# sanziqi_v1_2.net
KiCad netlist of a schematic drawn in Altium Designer
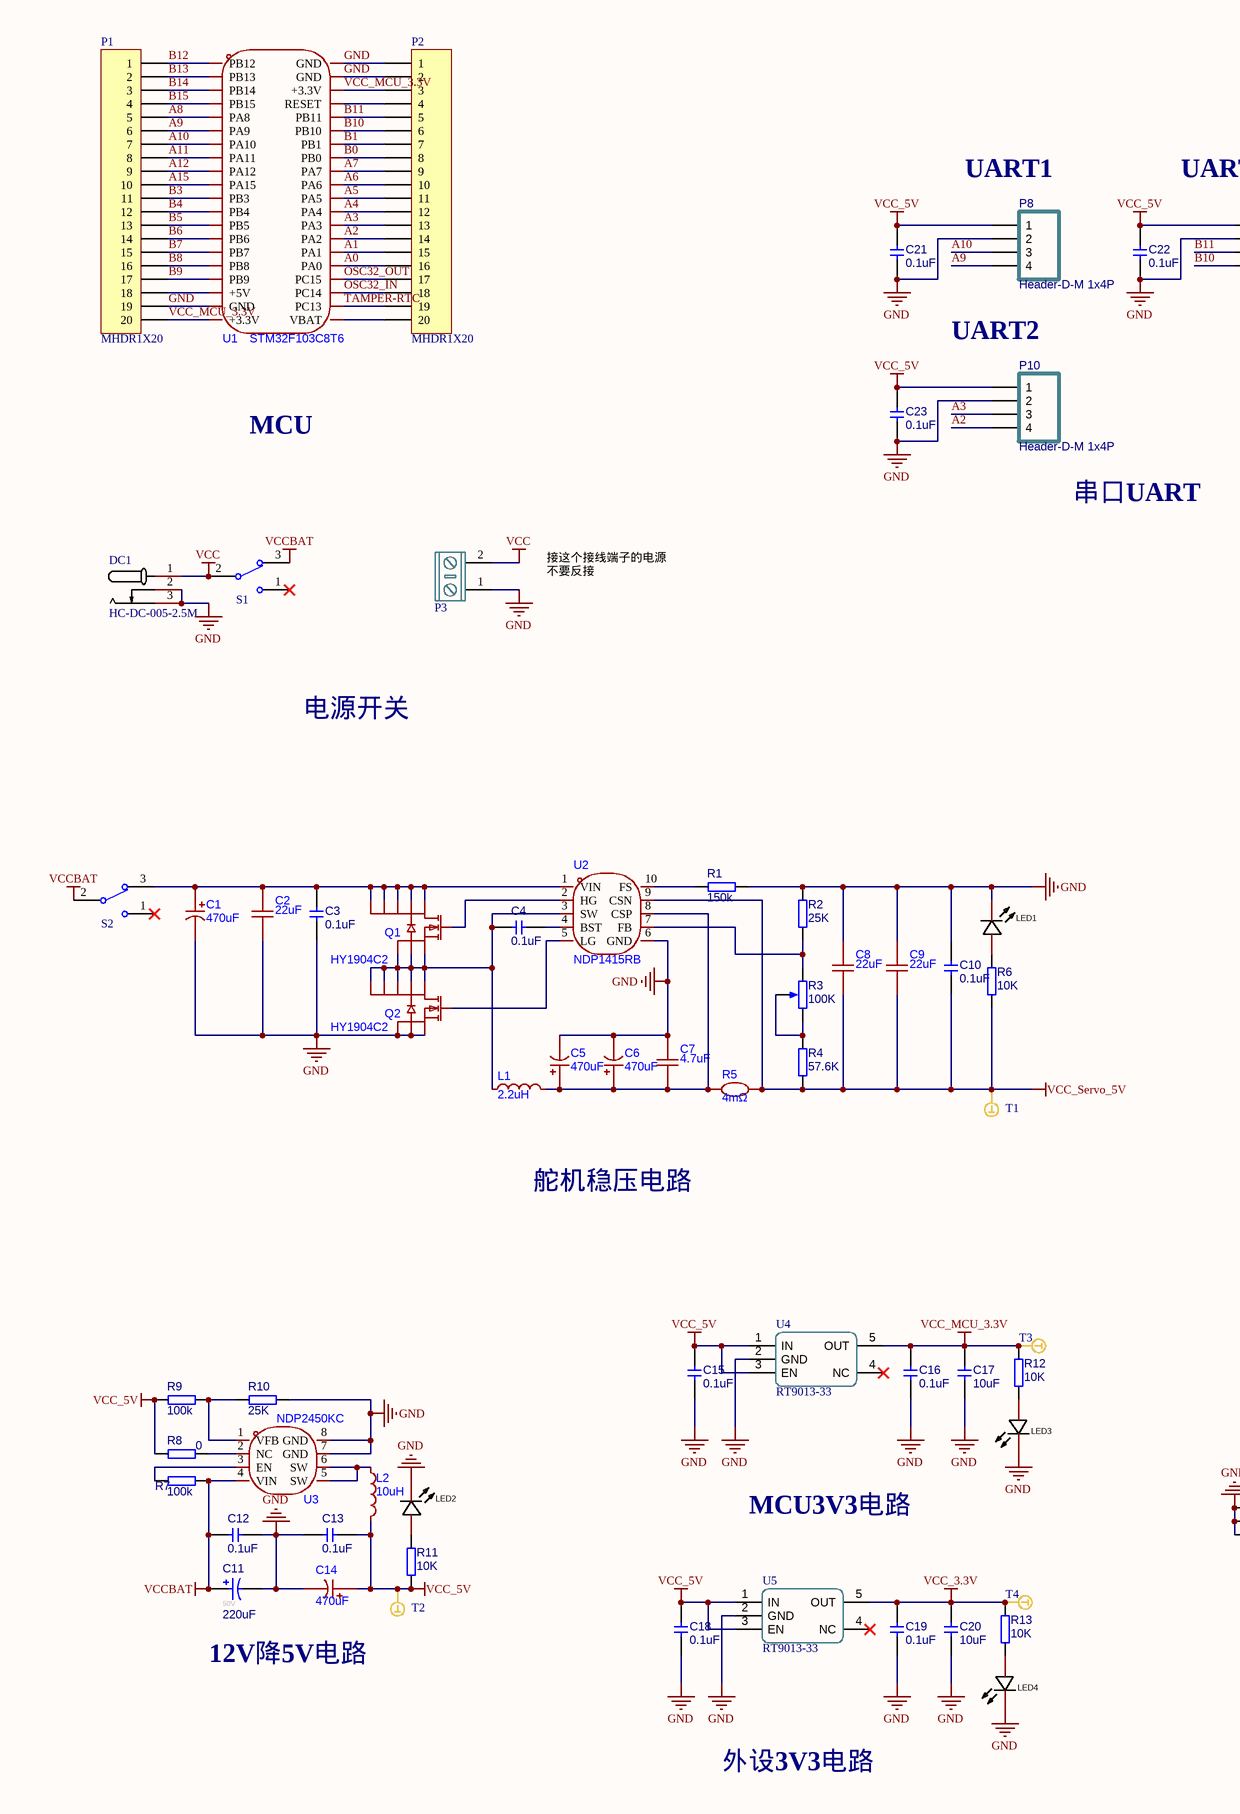
[diagram p0: sanziqi_v1.2.SchDoc, left]
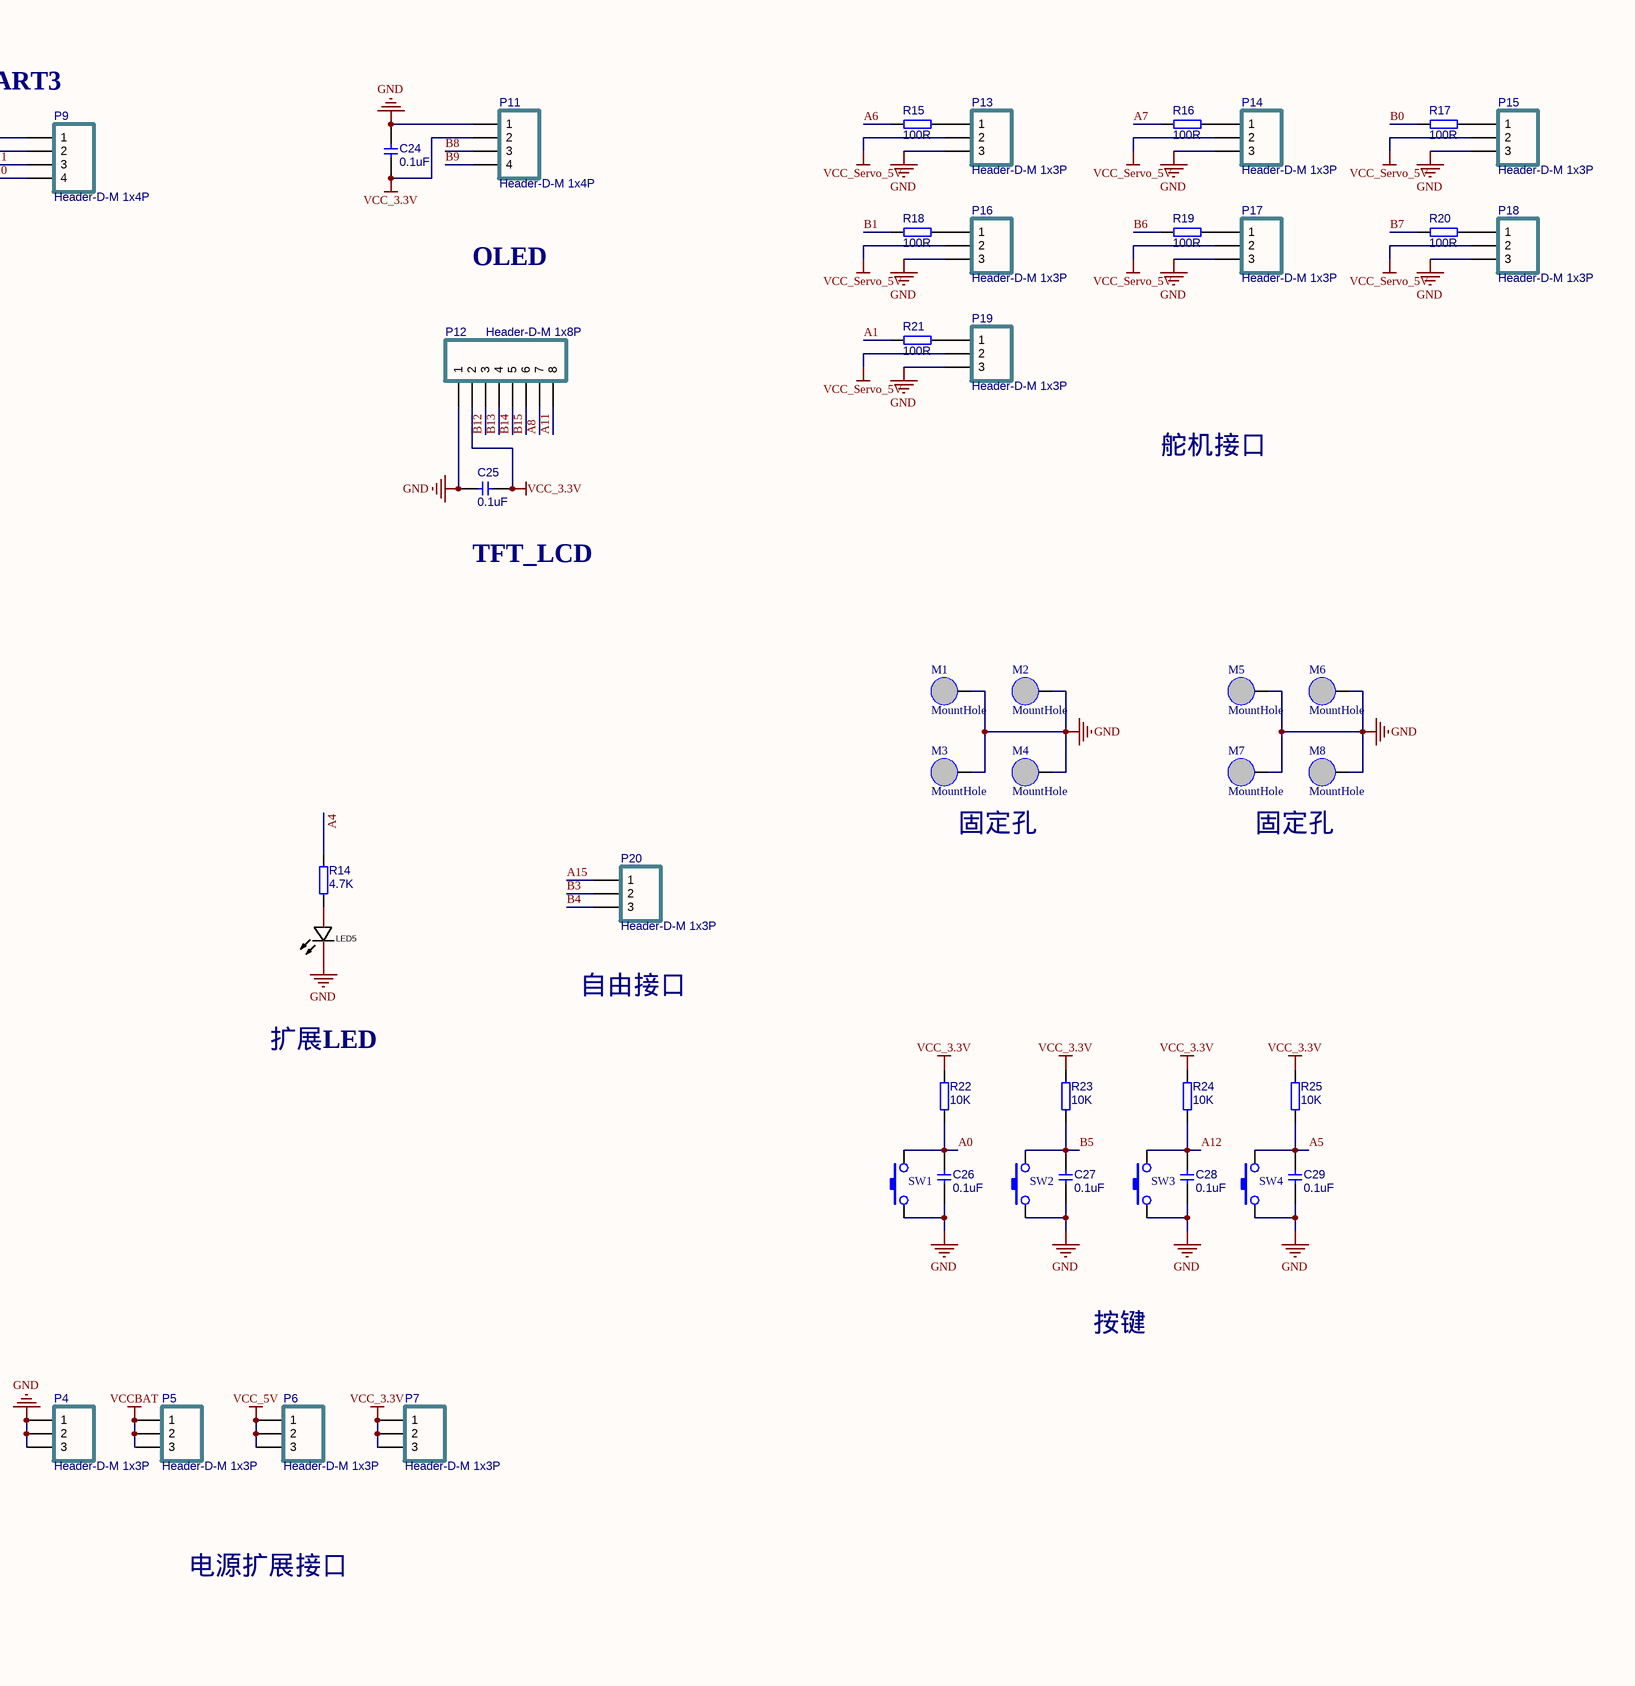
[diagram p1: sanziqi_v1.2.SchDoc, right]

(export (version "E")
  (design (tool "Eeschema 10.0.6"))
  (components
    (comp (ref "C1")
      (value "470uF")
      (footprint "CAP-TH_BD10.0-P5.00-D0.6-FD")
      (description "直插固态电容 470UF")
      (fields (field (name "MANUFACTURER") "HONOR(荣誉)") (field (name "MANUFACTURER PART") "HG1H477M1016PC"))
      (libsource (lib "sanziqi_v1.2") (part "HG1H477M1016PC"))
    )
    (comp (ref "C2")
      (value "22uF")
      (footprint "C1206")
      (fields
        (field (name "MANUFACTURER") "HRE(芯声)")
        (field (name "MANUFACTURER PART") "CGA1206X5R226M350NT")
        (field (name "TOLERANCE") "±20%")
      )
      (libsource (lib "sanziqi_v1.2") (part "Cap 22uF 1206"))
    )
    (comp (ref "C3")
      (value "0.1uF")
      (footprint "C0805")
      (description "贴片电容0805")
      (fields (field (name "Comment") "0.1uF  "))
      (libsource (lib "sanziqi_v1.2") (part "Cap 0.1uF 0805"))
    )
    (comp (ref "C4")
      (value "0.1uF")
      (footprint "C0805")
      (description "贴片电容0805")
      (fields (field (name "Comment") "0.1uF  "))
      (libsource (lib "sanziqi_v1.2") (part "Cap 0.1uF 0805"))
    )
    (comp (ref "C5")
      (value "470uF")
      (footprint "CAP-TH_BD10.0-P5.00-D0.6-FD")
      (description "直插固态电容 470UF")
      (fields (field (name "MANUFACTURER") "HONOR(荣誉)") (field (name "MANUFACTURER PART") "HG1H477M1016PC"))
      (libsource (lib "sanziqi_v1.2") (part "HG1H477M1016PC"))
    )
    (comp (ref "C6")
      (value "470uF")
      (footprint "CAP-TH_BD10.0-P5.00-D0.6-FD")
      (description "直插固态电容 470UF")
      (fields (field (name "MANUFACTURER") "HONOR(荣誉)") (field (name "MANUFACTURER PART") "HG1H477M1016PC"))
      (libsource (lib "sanziqi_v1.2") (part "HG1H477M1016PC"))
    )
    (comp (ref "C7")
      (value "4.7uF")
      (footprint "C1206")
      (fields
        (field (name "MANUFACTURER") "HRE(芯声)")
        (field (name "MANUFACTURER PART") "CGA1206X5R226M350NT")
        (field (name "TOLERANCE") "±20%")
      )
      (libsource (lib "sanziqi_v1.2") (part "Cap 22uF 1206"))
    )
    (comp (ref "C8")
      (value "22uF")
      (footprint "C1206")
      (fields
        (field (name "MANUFACTURER") "HRE(芯声)")
        (field (name "MANUFACTURER PART") "CGA1206X5R226M350NT")
        (field (name "TOLERANCE") "±20%")
      )
      (libsource (lib "sanziqi_v1.2") (part "Cap 22uF 1206"))
    )
    (comp (ref "C9")
      (value "22uF")
      (footprint "C1206")
      (fields
        (field (name "MANUFACTURER") "HRE(芯声)")
        (field (name "MANUFACTURER PART") "CGA1206X5R226M350NT")
        (field (name "TOLERANCE") "±20%")
      )
      (libsource (lib "sanziqi_v1.2") (part "Cap 22uF 1206"))
    )
    (comp (ref "C10")
      (value "0.1uF")
      (footprint "C0805")
      (description "贴片电容0805")
      (fields (field (name "Comment") "0.1uF  "))
      (libsource (lib "sanziqi_v1.2") (part "Cap 0.1uF 0805"))
    )
    (comp (ref "C11")
      (value "220uF")
      (footprint "CAP-TH_BD8.0-P3.50-D0.6-FD")
      (description "直插电解电容 220uF")
      (fields (field (name "VOLTAGE") "50V") (field (name "Comment") "220uF 50V 铝电解"))
      (libsource (lib "sanziqi_v1.2") (part "220uF 50V"))
    )
    (comp (ref "C12")
      (value "0.1uF")
      (footprint "C0805")
      (description "贴片电容0805")
      (fields (field (name "Comment") "0.1uF  "))
      (libsource (lib "sanziqi_v1.2") (part "0.1uF 0805"))
    )
    (comp (ref "C13")
      (value "0.1uF")
      (footprint "C0805")
      (description "贴片电容0805")
      (fields (field (name "Comment") "0.1uF  "))
      (libsource (lib "sanziqi_v1.2") (part "0.1uF 0805"))
    )
    (comp (ref "C14")
      (value "470uF")
      (footprint "CAP-TH_BD10.0-P5.00-D0.6-FD")
      (description "直插固态电容 470UF")
      (fields (field (name "MANUFACTURER") "HONOR(荣誉)") (field (name "MANUFACTURER PART") "HG1H477M1016PC"))
      (libsource (lib "sanziqi_v1.2") (part "HG1H477M1016PC"))
    )
    (comp (ref "C15")
      (value "0.1uF")
      (footprint "C0805")
      (description "贴片电容0805")
      (fields (field (name "Comment") "0.1uF  "))
      (libsource (lib "sanziqi_v1.2") (part "Cap 0.1uF 0805"))
    )
    (comp (ref "C16")
      (value "0.1uF")
      (footprint "C0805")
      (description "贴片电容0805")
      (fields (field (name "Comment") "0.1uF  "))
      (libsource (lib "sanziqi_v1.2") (part "Cap 0.1uF 0805"))
    )
    (comp (ref "C17")
      (value "10uF")
      (footprint "C0805")
      (description "贴片电容0805")
      (fields (field (name "Comment") "10uF  "))
      (libsource (lib "sanziqi_v1.2") (part "Cap 10uF 0805"))
    )
    (comp (ref "C18")
      (value "0.1uF")
      (footprint "C0805")
      (description "贴片电容0805")
      (fields (field (name "Comment") "0.1uF  "))
      (libsource (lib "sanziqi_v1.2") (part "Cap 0.1uF 0805"))
    )
    (comp (ref "C19")
      (value "0.1uF")
      (footprint "C0805")
      (description "贴片电容0805")
      (fields (field (name "Comment") "0.1uF  "))
      (libsource (lib "sanziqi_v1.2") (part "Cap 0.1uF 0805"))
    )
    (comp (ref "C20")
      (value "10uF")
      (footprint "C0805")
      (description "贴片电容0805")
      (fields (field (name "Comment") "10uF  "))
      (libsource (lib "sanziqi_v1.2") (part "Cap 10uF 0805"))
    )
    (comp (ref "C21")
      (value "0.1uF")
      (footprint "C0805")
      (description "贴片电容0805")
      (fields (field (name "Comment") "0.1uF  "))
      (libsource (lib "sanziqi_v1.2") (part "Cap 0.1uF 0805"))
    )
    (comp (ref "C22")
      (value "0.1uF")
      (footprint "C0805")
      (description "贴片电容0805")
      (fields (field (name "Comment") "0.1uF  "))
      (libsource (lib "sanziqi_v1.2") (part "Cap 0.1uF 0805"))
    )
    (comp (ref "C23")
      (value "0.1uF")
      (footprint "C0805")
      (description "贴片电容0805")
      (fields (field (name "Comment") "0.1uF  "))
      (libsource (lib "sanziqi_v1.2") (part "Cap 0.1uF 0805"))
    )
    (comp (ref "C24")
      (value "0.1uF")
      (footprint "C0805")
      (description "贴片电容0805")
      (fields (field (name "Comment") "0.1uF  "))
      (libsource (lib "sanziqi_v1.2") (part "Cap 0.1uF 0805"))
    )
    (comp (ref "C25")
      (value "0.1uF")
      (footprint "C0805")
      (description "贴片电容0805")
      (fields (field (name "Comment") "0.1uF  "))
      (libsource (lib "sanziqi_v1.2") (part "Cap 0.1uF 0805"))
    )
    (comp (ref "C26")
      (value "0.1uF")
      (footprint "C0805")
      (description "贴片电容0805")
      (fields (field (name "Comment") "0.1uF  "))
      (libsource (lib "sanziqi_v1.2") (part "Cap 0.1uF 0805"))
    )
    (comp (ref "C27")
      (value "0.1uF")
      (footprint "C0805")
      (description "贴片电容0805")
      (fields (field (name "Comment") "0.1uF  "))
      (libsource (lib "sanziqi_v1.2") (part "Cap 0.1uF 0805"))
    )
    (comp (ref "C28")
      (value "0.1uF")
      (footprint "C0805")
      (description "贴片电容0805")
      (fields (field (name "Comment") "0.1uF  "))
      (libsource (lib "sanziqi_v1.2") (part "Cap 0.1uF 0805"))
    )
    (comp (ref "C29")
      (value "0.1uF")
      (footprint "C0805")
      (description "贴片电容0805")
      (fields (field (name "Comment") "0.1uF  "))
      (libsource (lib "sanziqi_v1.2") (part "Cap 0.1uF 0805"))
    )
    (comp (ref "DC1")
      (value "HC-DC-005-2.5M")
      (footprint "DC-005")
      (fields (field (name "MANUFACTURER") "HCTL(华灿天禄)") (field (name "NAME") "HC-DC-005-2.5M"))
      (libsource (lib "sanziqi_v1.2") (part "HC-DC-005-2.5M"))
    )
    (comp (ref "L1")
      (value "2.2uH")
      (footprint "IND-SMD_L11.5-W10.0_FXL1040")
      (fields
        (field (name "MANUFACTURER") "cjiang(长江微电)")
        (field (name "MANUFACTURER PART") "FXL1050-2R2-M")
        (field (name "TOLERANCE") "±20%")
      )
      (libsource (lib "sanziqi_v1.2") (part "FXL1050-2R2-M"))
    )
    (comp (ref "L2")
      (value "10uH")
      (footprint "IND-SMD_L11.5-W10.0_FXL1040")
      (fields
        (field (name "MANUFACTURER") "cjiang(长江微电)")
        (field (name "MANUFACTURER PART") "FXL1040-100-M")
        (field (name "TOLERANCE") "±20%")
      )
      (libsource (lib "sanziqi_v1.2") (part "FXL1040-100-M"))
    )
    (comp (ref "LED1")
      (value "NCD0805R1")
      (footprint "LED0805-R-RD")
      (fields (field (name "MANUFACTURER") "国星光电"))
      (libsource (lib "sanziqi_v1.2") (part "LED"))
    )
    (comp (ref "LED2")
      (value "NCD0805R1")
      (footprint "LED0805-R-RD")
      (fields (field (name "MANUFACTURER") "国星光电"))
      (libsource (lib "sanziqi_v1.2") (part "LED"))
    )
    (comp (ref "LED3")
      (value "NCD0805R1")
      (footprint "LED0805-R-RD")
      (fields (field (name "MANUFACTURER") "国星光电"))
      (libsource (lib "sanziqi_v1.2") (part "LED"))
    )
    (comp (ref "LED4")
      (value "NCD0805R1")
      (footprint "LED0805-R-RD")
      (fields (field (name "MANUFACTURER") "国星光电"))
      (libsource (lib "sanziqi_v1.2") (part "LED"))
    )
    (comp (ref "LED5")
      (value "NCD0805R1")
      (footprint "LED0805-R-RD")
      (fields (field (name "MANUFACTURER") "国星光电"))
      (libsource (lib "sanziqi_v1.2") (part "LED"))
    )
    (comp (ref "M1")
      (value "MountHole")
      (footprint "M3-MountHole")
      (description "固定孔")
      (libsource (lib "sanziqi_v1.2") (part "MountHole"))
    )
    (comp (ref "M2")
      (value "MountHole")
      (footprint "M3-MountHole")
      (description "固定孔")
      (libsource (lib "sanziqi_v1.2") (part "MountHole"))
    )
    (comp (ref "M3")
      (value "MountHole")
      (footprint "M3-MountHole")
      (description "固定孔")
      (libsource (lib "sanziqi_v1.2") (part "MountHole"))
    )
    (comp (ref "M4")
      (value "MountHole")
      (footprint "M3-MountHole")
      (description "固定孔")
      (libsource (lib "sanziqi_v1.2") (part "MountHole"))
    )
    (comp (ref "M5")
      (value "MountHole")
      (footprint "M3-MountHole")
      (description "固定孔")
      (libsource (lib "sanziqi_v1.2") (part "MountHole"))
    )
    (comp (ref "M6")
      (value "MountHole")
      (footprint "M3-MountHole")
      (description "固定孔")
      (libsource (lib "sanziqi_v1.2") (part "MountHole"))
    )
    (comp (ref "M7")
      (value "MountHole")
      (footprint "M3-MountHole")
      (description "固定孔")
      (libsource (lib "sanziqi_v1.2") (part "MountHole"))
    )
    (comp (ref "M8")
      (value "MountHole")
      (footprint "M3-MountHole")
      (description "固定孔")
      (libsource (lib "sanziqi_v1.2") (part "MountHole"))
    )
    (comp (ref "P1")
      (value "MHDR1X20")
      (footprint "HDR2.54-LI-20P")
      (description "Header, 20-Pin")
      (fields (field (name "PUBLISHER") "Altium Limited"))
      (libsource (lib "sanziqi_v1.2") (part "MHDR1X20"))
    )
    (comp (ref "P2")
      (value "MHDR1X20")
      (footprint "HDR2.54-LI-20P")
      (description "Header, 20-Pin")
      (fields (field (name "PUBLISHER") "Altium Limited"))
      (libsource (lib "") (part "MHDR1X20_1"))
    )
    (comp (ref "P3")
      (value "KF/WJ/DG 30x connecter")
      (footprint "KF/WJ/DG 301-2p-5.0mm")
      (description "接线端子 2Pin")
      (libsource (lib "sanziqi_v1.2") (part "KF/WJ/DG 30x"))
    )
    (comp (ref "P4")
      (value "Header-D-M 1x3P")
      (footprint "HDR1X3-M")
      (description "1x3pin, 直插, 排针")
      (libsource (lib "sanziqi_v1.2") (part "Header-D-M 1x3P"))
    )
    (comp (ref "P5")
      (value "Header-D-M 1x3P")
      (footprint "HDR1X3-M")
      (description "1x3pin, 直插, 排针")
      (libsource (lib "sanziqi_v1.2") (part "Header-D-M 1x3P"))
    )
    (comp (ref "P6")
      (value "Header-D-M 1x3P")
      (footprint "HDR1X3-M")
      (description "1x3pin, 直插, 排针")
      (libsource (lib "sanziqi_v1.2") (part "Header-D-M 1x3P"))
    )
    (comp (ref "P7")
      (value "Header-D-M 1x3P")
      (footprint "HDR1X3-M")
      (description "1x3pin, 直插, 排针")
      (libsource (lib "sanziqi_v1.2") (part "Header-D-M 1x3P"))
    )
    (comp (ref "P8")
      (value "Header-D-M 1x4P")
      (footprint "HDR1X4-M")
      (description "1x4pin, 直插, 排针")
      (libsource (lib "sanziqi_v1.2") (part "Header-D-M 1x4P"))
    )
    (comp (ref "P9")
      (value "Header-D-M 1x4P")
      (footprint "HDR1X4-M")
      (description "1x4pin, 直插, 排针")
      (libsource (lib "sanziqi_v1.2") (part "Header-D-M 1x4P"))
    )
    (comp (ref "P10")
      (value "Header-D-M 1x4P")
      (footprint "HDR1X4-M")
      (description "1x4pin, 直插, 排针")
      (libsource (lib "sanziqi_v1.2") (part "Header-D-M 1x4P"))
    )
    (comp (ref "P11")
      (value "Header-D-M 1x4P")
      (footprint "HDR1X4-M")
      (description "1x4pin, 直插, 排针")
      (libsource (lib "sanziqi_v1.2") (part "Header-D-M 1x4P"))
    )
    (comp (ref "P12")
      (value "Header-D-M 1x8P")
      (footprint "HDR1X8-M")
      (description "1x8pin, 直插, 排针")
      (libsource (lib "sanziqi_v1.2") (part "Header-D-M 1x8P"))
    )
    (comp (ref "P13")
      (value "Header-D-M 1x3P")
      (footprint "HDR1X3-M")
      (description "1x3pin, 直插, 排针")
      (libsource (lib "sanziqi_v1.2") (part "Header-D-M 1x3P"))
    )
    (comp (ref "P14")
      (value "Header-D-M 1x3P")
      (footprint "HDR1X3-M")
      (description "1x3pin, 直插, 排针")
      (libsource (lib "sanziqi_v1.2") (part "Header-D-M 1x3P"))
    )
    (comp (ref "P15")
      (value "Header-D-M 1x3P")
      (footprint "HDR1X3-M")
      (description "1x3pin, 直插, 排针")
      (libsource (lib "sanziqi_v1.2") (part "Header-D-M 1x3P"))
    )
    (comp (ref "P16")
      (value "Header-D-M 1x3P")
      (footprint "HDR1X3-M")
      (description "1x3pin, 直插, 排针")
      (libsource (lib "sanziqi_v1.2") (part "Header-D-M 1x3P"))
    )
    (comp (ref "P17")
      (value "Header-D-M 1x3P")
      (footprint "HDR1X3-M")
      (description "1x3pin, 直插, 排针")
      (libsource (lib "sanziqi_v1.2") (part "Header-D-M 1x3P"))
    )
    (comp (ref "P18")
      (value "Header-D-M 1x3P")
      (footprint "HDR1X3-M")
      (description "1x3pin, 直插, 排针")
      (libsource (lib "sanziqi_v1.2") (part "Header-D-M 1x3P"))
    )
    (comp (ref "P19")
      (value "Header-D-M 1x3P")
      (footprint "HDR1X3-M")
      (description "1x3pin, 直插, 排针")
      (libsource (lib "sanziqi_v1.2") (part "Header-D-M 1x3P"))
    )
    (comp (ref "P20")
      (value "Header-D-M 1x3P")
      (footprint "HDR1X3-M")
      (description "1x3pin, 直插, 排针")
      (libsource (lib "sanziqi_v1.2") (part "Header-D-M 1x3P"))
    )
    (comp (ref "Q1")
      (value "HY1904C2")
      (footprint "DFN-8_L5.9-W5.2-P1.27-LS6.2-BL")
      (fields (field (name "MANUFACTURER") "HUAYI(华羿微)"))
      (libsource (lib "sanziqi_v1.2") (part "HY1904C2"))
    )
    (comp (ref "Q2")
      (value "HY1904C2")
      (footprint "DFN-8_L5.9-W5.2-P1.27-LS6.2-BL")
      (fields (field (name "MANUFACTURER") "HUAYI(华羿微)"))
      (libsource (lib "sanziqi_v1.2") (part "HY1904C2"))
    )
    (comp (ref "R1")
      (value "150k")
      (footprint "R0805")
      (description "贴片电阻")
      (fields (field (name "POWER") "1/8W") (field (name "TOLERANCE") "±1%"))
      (libsource (lib "sanziqi_v1.2") (part "Res-Chip-150K"))
    )
    (comp (ref "R2")
      (value "25K")
      (footprint "R0805")
      (description "贴片电阻")
      (fields (field (name "POWER") "1/8W") (field (name "TOLERANCE") "±1%"))
      (libsource (lib "sanziqi_v1.2") (part "Res-Chip-25K"))
    )
    (comp (ref "R3")
      (value "100K")
      (footprint "RESPOT3296W")
      (description "可调电阻")
      (libsource (lib "sanziqi_v1.2") (part "Res-Adj-3p"))
    )
    (comp (ref "R4")
      (value "57.6K")
      (footprint "R0805")
      (description "贴片电阻")
      (fields (field (name "POWER") "1/8W") (field (name "TOLERANCE") "±1%"))
      (libsource (lib "sanziqi_v1.2") (part "Res-Chip-57.6K"))
    )
    (comp (ref "R5")
      (value "4mΩ")
      (footprint "RES-SMD_L6.4-W3.2-R2512")
      (fields
        (field (name "MANUFACTURER") "Milliohm(毫欧)")
        (field (name "MANUFACTURER PART") "HoJLR2512-3W-4mR-1%")
        (field (name "TOLERANCE") "±1%")
      )
      (libsource (lib "sanziqi_v1.2") (part "Res-Chip-4mR-2512-3W"))
    )
    (comp (ref "R6")
      (value "10K")
      (footprint "R0805")
      (description "贴片电阻")
      (fields (field (name "POWER") "1/8W") (field (name "TOLERANCE") "±1%"))
      (libsource (lib "sanziqi_v1.2") (part "Res-Chip-4.7K"))
    )
    (comp (ref "R7")
      (value "100k")
      (footprint "R0805")
      (description "贴片电阻")
      (fields (field (name "POWER") "1/8W") (field (name "TOLERANCE") "±1%"))
      (libsource (lib "sanziqi_v1.2") (part "Res-Chip-100K"))
    )
    (comp (ref "R8")
      (value "0")
      (footprint "R0805")
      (description "贴片电阻")
      (fields (field (name "POWER") "1/8W") (field (name "TOLERANCE") "±1%"))
      (libsource (lib "sanziqi_v1.2") (part "Res-Chip-0"))
    )
    (comp (ref "R9")
      (value "100k")
      (footprint "R0805")
      (description "贴片电阻")
      (fields (field (name "POWER") "1/8W") (field (name "TOLERANCE") "±1%"))
      (libsource (lib "sanziqi_v1.2") (part "Res-Chip-100K"))
    )
    (comp (ref "R10")
      (value "25K")
      (footprint "R0805")
      (description "贴片电阻")
      (fields (field (name "POWER") "1/8W") (field (name "TOLERANCE") "±1%"))
      (libsource (lib "sanziqi_v1.2") (part "Res-Chip-25K"))
    )
    (comp (ref "R11")
      (value "10K")
      (footprint "R0805")
      (description "贴片电阻")
      (fields (field (name "POWER") "1/8W") (field (name "TOLERANCE") "±1%"))
      (libsource (lib "sanziqi_v1.2") (part "Res-Chip-4.7K"))
    )
    (comp (ref "R12")
      (value "10K")
      (footprint "R0805")
      (description "贴片电阻")
      (fields (field (name "POWER") "1/8W") (field (name "TOLERANCE") "±1%"))
      (libsource (lib "sanziqi_v1.2") (part "Res-Chip-4.7K"))
    )
    (comp (ref "R13")
      (value "10K")
      (footprint "R0805")
      (description "贴片电阻")
      (fields (field (name "POWER") "1/8W") (field (name "TOLERANCE") "±1%"))
      (libsource (lib "sanziqi_v1.2") (part "Res-Chip-4.7K"))
    )
    (comp (ref "R14")
      (value "4.7K")
      (footprint "R0805")
      (description "贴片电阻")
      (fields (field (name "POWER") "1/8W") (field (name "TOLERANCE") "±1%"))
      (libsource (lib "sanziqi_v1.2") (part "Res-Chip-4.7K"))
    )
    (comp (ref "R15")
      (value "100R")
      (footprint "R0805")
      (description "贴片电阻")
      (fields (field (name "POWER") "1/8W") (field (name "TOLERANCE") "±1%"))
      (libsource (lib "sanziqi_v1.2") (part "Res-Chip-100R"))
    )
    (comp (ref "R16")
      (value "100R")
      (footprint "R0805")
      (description "贴片电阻")
      (fields (field (name "POWER") "1/8W") (field (name "TOLERANCE") "±1%"))
      (libsource (lib "sanziqi_v1.2") (part "Res-Chip-100R"))
    )
    (comp (ref "R17")
      (value "100R")
      (footprint "R0805")
      (description "贴片电阻")
      (fields (field (name "POWER") "1/8W") (field (name "TOLERANCE") "±1%"))
      (libsource (lib "sanziqi_v1.2") (part "Res-Chip-100R"))
    )
    (comp (ref "R18")
      (value "100R")
      (footprint "R0805")
      (description "贴片电阻")
      (fields (field (name "POWER") "1/8W") (field (name "TOLERANCE") "±1%"))
      (libsource (lib "sanziqi_v1.2") (part "Res-Chip-100R"))
    )
    (comp (ref "R19")
      (value "100R")
      (footprint "R0805")
      (description "贴片电阻")
      (fields (field (name "POWER") "1/8W") (field (name "TOLERANCE") "±1%"))
      (libsource (lib "sanziqi_v1.2") (part "Res-Chip-100R"))
    )
    (comp (ref "R20")
      (value "100R")
      (footprint "R0805")
      (description "贴片电阻")
      (fields (field (name "POWER") "1/8W") (field (name "TOLERANCE") "±1%"))
      (libsource (lib "sanziqi_v1.2") (part "Res-Chip-100R"))
    )
    (comp (ref "R21")
      (value "100R")
      (footprint "R0805")
      (description "贴片电阻")
      (fields (field (name "POWER") "1/8W") (field (name "TOLERANCE") "±1%"))
      (libsource (lib "sanziqi_v1.2") (part "Res-Chip-100R"))
    )
    (comp (ref "R22")
      (value "10K")
      (footprint "R0805")
      (description "贴片电阻")
      (fields (field (name "POWER") "1/8W") (field (name "TOLERANCE") "±1%"))
      (libsource (lib "sanziqi_v1.2") (part "Res-Chip-10K"))
    )
    (comp (ref "R23")
      (value "10K")
      (footprint "R0805")
      (description "贴片电阻")
      (fields (field (name "POWER") "1/8W") (field (name "TOLERANCE") "±1%"))
      (libsource (lib "sanziqi_v1.2") (part "Res-Chip-10K"))
    )
    (comp (ref "R24")
      (value "10K")
      (footprint "R0805")
      (description "贴片电阻")
      (fields (field (name "POWER") "1/8W") (field (name "TOLERANCE") "±1%"))
      (libsource (lib "sanziqi_v1.2") (part "Res-Chip-10K"))
    )
    (comp (ref "R25")
      (value "10K")
      (footprint "R0805")
      (description "贴片电阻")
      (fields (field (name "POWER") "1/8W") (field (name "TOLERANCE") "±1%"))
      (libsource (lib "sanziqi_v1.2") (part "Res-Chip-10K"))
    )
    (comp (ref "S1")
      (value "SW-SPDT")
      (footprint "SS12D10")
      (description "单刀双掷开关 3脚船型、钮子、拨动开关 SPDT Subminiature Toggle Switch")
      (fields (field (name "PUBLISHER") "Altium Limited"))
      (libsource (lib "sanziqi_v1.2") (part "SW-SPDT"))
    )
    (comp (ref "S2")
      (value "SW-SPDT")
      (footprint "SS12D10")
      (description "单刀双掷开关 3脚船型、钮子、拨动开关 SPDT Subminiature Toggle Switch")
      (fields (field (name "PUBLISHER") "Altium Limited"))
      (libsource (lib "sanziqi_v1.2") (part "SW-SPDT"))
    )
    (comp (ref "SW1")
      (value "SW-PB_V")
      (footprint "TSW SMD-3*6*2.5")
      (description "SWITCH")
      (libsource (lib "sanziqi_v1.2") (part "SW-PB_V"))
    )
    (comp (ref "SW2")
      (value "SW-PB_V")
      (footprint "TSW SMD-3*6*2.5")
      (description "SWITCH")
      (libsource (lib "sanziqi_v1.2") (part "SW-PB_V"))
    )
    (comp (ref "SW3")
      (value "SW-PB_V")
      (footprint "TSW SMD-3*6*2.5")
      (description "SWITCH")
      (libsource (lib "sanziqi_v1.2") (part "SW-PB_V"))
    )
    (comp (ref "SW4")
      (value "SW-PB_V")
      (footprint "TSW SMD-3*6*2.5")
      (description "SWITCH")
      (libsource (lib "sanziqi_v1.2") (part "SW-PB_V"))
    )
    (comp (ref "T1")
      (value "Testpoint-Pad")
      (footprint "testpoint-pad-1mm")
      (description "测试点，就是个焊盘")
      (libsource (lib "sanziqi_v1.2") (part "Testpoint-Pad-S"))
    )
    (comp (ref "T2")
      (value "Testpoint-Pad")
      (footprint "testpoint-pad-1mm")
      (description "测试点，就是个焊盘")
      (libsource (lib "sanziqi_v1.2") (part "Testpoint-Pad-S"))
    )
    (comp (ref "T3")
      (value "Testpoint-Pad")
      (footprint "testpoint-pad-1mm")
      (description "测试点，就是个焊盘")
      (libsource (lib "sanziqi_v1.2") (part "Testpoint-Pad-S"))
    )
    (comp (ref "T4")
      (value "Testpoint-Pad")
      (footprint "testpoint-pad-1mm")
      (description "测试点，就是个焊盘")
      (libsource (lib "sanziqi_v1.2") (part "Testpoint-Pad-S"))
    )
    (comp (ref "U1")
      (value "STM32F103C8T6")
      (footprint "CONN-TH_L53.3-W22.9_STM32F103C8T6-CARD")
      (fields
        (field (name "MANUFACTURER") "立创开发板")
        (field (name "MANUFACTURER PART") "LCKFB-DKX-STM32F103C8T6")
      )
      (libsource (lib "sanziqi_v1.2") (part "STM32F103C8T6"))
    )
    (comp (ref "U2")
      (value "NDP1415RB")
      (footprint "SSOP-10_L4.9-W3.9-P1.00-LS6.0-BL-1")
      (fields (field (name "MANUFACTURER") "NDP(芯潭微)"))
      (libsource (lib "sanziqi_v1.2") (part "NDP1415RB"))
    )
    (comp (ref "U3")
      (value "NDP2450KC")
      (footprint "SOP-8_L4.9-W3.9-P1.27-LS6.0-BL")
      (fields (field (name "MANUFACTURER") "NDP(芯潭微)"))
      (libsource (lib "sanziqi_v1.2") (part "NDP2450KC"))
    )
    (comp (ref "U4")
      (value "RT9013-33")
      (footprint "SOT-23-5")
      (description "3.3V 500mA SOT-23-5 LDO")
      (libsource (lib "sanziqi_v1.2") (part "RT9013-33"))
    )
    (comp (ref "U5")
      (value "RT9013-33")
      (footprint "SOT-23-5")
      (description "3.3V 500mA SOT-23-5 LDO")
      (libsource (lib "sanziqi_v1.2") (part "RT9013-33"))
    )
  )
  (nets
    (net (code "1") (name "/A0") (class "Default")
      (node (ref "C26") (pin "2") (pinfunction "2_2") (pintype "passive"))
      (node (ref "P2") (pin "16") (pinfunction "16_16") (pintype "passive"))
      (node (ref "R22") (pin "1") (pinfunction "1_1") (pintype "passive"))
      (node (ref "SW1") (pin "2") (pinfunction "2_2") (pintype "passive"))
      (node (ref "U1") (pin "25") (pinfunction "PA0_25") (pintype "passive"))
    )
    (net (code "2") (name "/A1") (class "Default")
      (node (ref "P2") (pin "15") (pinfunction "15_15") (pintype "passive"))
      (node (ref "R21") (pin "1") (pinfunction "1_1") (pintype "passive"))
      (node (ref "U1") (pin "26") (pinfunction "PA1_26") (pintype "passive"))
    )
    (net (code "3") (name "/A2") (class "Default")
      (node (ref "P10") (pin "4") (pinfunction "4_4") (pintype "passive"))
      (node (ref "P2") (pin "14") (pinfunction "14_14") (pintype "passive"))
      (node (ref "U1") (pin "27") (pinfunction "PA2_27") (pintype "passive"))
    )
    (net (code "4") (name "/A3") (class "Default")
      (node (ref "P10") (pin "3") (pinfunction "3_3") (pintype "passive"))
      (node (ref "P2") (pin "13") (pinfunction "13_13") (pintype "passive"))
      (node (ref "U1") (pin "28") (pinfunction "PA3_28") (pintype "passive"))
    )
    (net (code "5") (name "/A4") (class "Default")
      (node (ref "P2") (pin "12") (pinfunction "12_12") (pintype "passive"))
      (node (ref "R14") (pin "2") (pinfunction "2_2") (pintype "passive"))
      (node (ref "U1") (pin "29") (pinfunction "PA4_29") (pintype "passive"))
    )
    (net (code "6") (name "/A5") (class "Default")
      (node (ref "C29") (pin "2") (pinfunction "2_2") (pintype "passive"))
      (node (ref "P2") (pin "11") (pinfunction "11_11") (pintype "passive"))
      (node (ref "R25") (pin "1") (pinfunction "1_1") (pintype "passive"))
      (node (ref "SW4") (pin "2") (pinfunction "2_2") (pintype "passive"))
      (node (ref "U1") (pin "30") (pinfunction "PA5_30") (pintype "passive"))
    )
    (net (code "7") (name "/A6") (class "Default")
      (node (ref "P2") (pin "10") (pinfunction "10_10") (pintype "passive"))
      (node (ref "R15") (pin "1") (pinfunction "1_1") (pintype "passive"))
      (node (ref "U1") (pin "31") (pinfunction "PA6_31") (pintype "passive"))
    )
    (net (code "8") (name "/A7") (class "Default")
      (node (ref "P2") (pin "9") (pinfunction "9_9") (pintype "passive"))
      (node (ref "R16") (pin "1") (pinfunction "1_1") (pintype "passive"))
      (node (ref "U1") (pin "32") (pinfunction "PA7_32") (pintype "passive"))
    )
    (net (code "9") (name "/A8") (class "Default")
      (node (ref "P1") (pin "5") (pinfunction "5_5") (pintype "passive"))
      (node (ref "P12") (pin "7") (pinfunction "7_7") (pintype "passive"))
      (node (ref "U1") (pin "5") (pinfunction "PA8_5") (pintype "passive"))
    )
    (net (code "10") (name "/A9") (class "Default")
      (node (ref "P1") (pin "6") (pinfunction "6_6") (pintype "passive"))
      (node (ref "P8") (pin "4") (pinfunction "4_4") (pintype "passive"))
      (node (ref "U1") (pin "6") (pinfunction "PA9_6") (pintype "passive"))
    )
    (net (code "11") (name "/A10") (class "Default")
      (node (ref "P1") (pin "7") (pinfunction "7_7") (pintype "passive"))
      (node (ref "P8") (pin "3") (pinfunction "3_3") (pintype "passive"))
      (node (ref "U1") (pin "7") (pinfunction "PA10_7") (pintype "passive"))
    )
    (net (code "12") (name "/A11") (class "Default")
      (node (ref "P1") (pin "8") (pinfunction "8_8") (pintype "passive"))
      (node (ref "P12") (pin "8") (pinfunction "8_8") (pintype "passive"))
      (node (ref "U1") (pin "8") (pinfunction "PA11_8") (pintype "passive"))
    )
    (net (code "13") (name "/A12") (class "Default")
      (node (ref "C28") (pin "2") (pinfunction "2_2") (pintype "passive"))
      (node (ref "P1") (pin "9") (pinfunction "9_9") (pintype "passive"))
      (node (ref "R24") (pin "1") (pinfunction "1_1") (pintype "passive"))
      (node (ref "SW3") (pin "2") (pinfunction "2_2") (pintype "passive"))
      (node (ref "U1") (pin "9") (pinfunction "PA12_9") (pintype "passive"))
    )
    (net (code "14") (name "/A15") (class "Default")
      (node (ref "P1") (pin "10") (pinfunction "10_10") (pintype "passive"))
      (node (ref "P20") (pin "1") (pinfunction "1_1") (pintype "passive"))
      (node (ref "U1") (pin "10") (pinfunction "PA15_10") (pintype "passive"))
    )
    (net (code "15") (name "/B0") (class "Default")
      (node (ref "P2") (pin "8") (pinfunction "8_8") (pintype "passive"))
      (node (ref "R17") (pin "1") (pinfunction "1_1") (pintype "passive"))
      (node (ref "U1") (pin "33") (pinfunction "PB0_33") (pintype "passive"))
    )
    (net (code "16") (name "/B1") (class "Default")
      (node (ref "P2") (pin "7") (pinfunction "7_7") (pintype "passive"))
      (node (ref "R18") (pin "1") (pinfunction "1_1") (pintype "passive"))
      (node (ref "U1") (pin "34") (pinfunction "PB1_34") (pintype "passive"))
    )
    (net (code "17") (name "/B3") (class "Default")
      (node (ref "P1") (pin "11") (pinfunction "11_11") (pintype "passive"))
      (node (ref "P20") (pin "2") (pinfunction "2_2") (pintype "passive"))
      (node (ref "U1") (pin "11") (pinfunction "PB3_11") (pintype "passive"))
    )
    (net (code "18") (name "/B4") (class "Default")
      (node (ref "P1") (pin "12") (pinfunction "12_12") (pintype "passive"))
      (node (ref "P20") (pin "3") (pinfunction "3_3") (pintype "passive"))
      (node (ref "U1") (pin "12") (pinfunction "PB4_12") (pintype "passive"))
    )
    (net (code "19") (name "/B5") (class "Default")
      (node (ref "C27") (pin "2") (pinfunction "2_2") (pintype "passive"))
      (node (ref "P1") (pin "13") (pinfunction "13_13") (pintype "passive"))
      (node (ref "R23") (pin "1") (pinfunction "1_1") (pintype "passive"))
      (node (ref "SW2") (pin "2") (pinfunction "2_2") (pintype "passive"))
      (node (ref "U1") (pin "13") (pinfunction "PB5_13") (pintype "passive"))
    )
    (net (code "20") (name "/B6") (class "Default")
      (node (ref "P1") (pin "14") (pinfunction "14_14") (pintype "passive"))
      (node (ref "R19") (pin "1") (pinfunction "1_1") (pintype "passive"))
      (node (ref "U1") (pin "14") (pinfunction "PB6_14") (pintype "passive"))
    )
    (net (code "21") (name "/B7") (class "Default")
      (node (ref "P1") (pin "15") (pinfunction "15_15") (pintype "passive"))
      (node (ref "R20") (pin "1") (pinfunction "1_1") (pintype "passive"))
      (node (ref "U1") (pin "15") (pinfunction "PB7_15") (pintype "passive"))
    )
    (net (code "22") (name "/B8") (class "Default")
      (node (ref "P1") (pin "16") (pinfunction "16_16") (pintype "passive"))
      (node (ref "P11") (pin "3") (pinfunction "3_3") (pintype "passive"))
      (node (ref "U1") (pin "16") (pinfunction "PB8_16") (pintype "passive"))
    )
    (net (code "23") (name "/B9") (class "Default")
      (node (ref "P1") (pin "17") (pinfunction "17_17") (pintype "passive"))
      (node (ref "P11") (pin "4") (pinfunction "4_4") (pintype "passive"))
      (node (ref "U1") (pin "17") (pinfunction "PB9_17") (pintype "passive"))
    )
    (net (code "24") (name "/B10") (class "Default")
      (node (ref "P2") (pin "6") (pinfunction "6_6") (pintype "passive"))
      (node (ref "P9") (pin "4") (pinfunction "4_4") (pintype "passive"))
      (node (ref "U1") (pin "35") (pinfunction "PB10_35") (pintype "passive"))
    )
    (net (code "25") (name "/B11") (class "Default")
      (node (ref "P2") (pin "5") (pinfunction "5_5") (pintype "passive"))
      (node (ref "P9") (pin "3") (pinfunction "3_3") (pintype "passive"))
      (node (ref "U1") (pin "36") (pinfunction "PB11_36") (pintype "passive"))
    )
    (net (code "26") (name "/B12") (class "Default")
      (node (ref "P1") (pin "1") (pinfunction "1_1") (pintype "passive"))
      (node (ref "P12") (pin "3") (pinfunction "3_3") (pintype "passive"))
      (node (ref "U1") (pin "1") (pinfunction "PB12_1") (pintype "passive"))
    )
    (net (code "27") (name "/B13") (class "Default")
      (node (ref "P1") (pin "2") (pinfunction "2_2") (pintype "passive"))
      (node (ref "P12") (pin "4") (pinfunction "4_4") (pintype "passive"))
      (node (ref "U1") (pin "2") (pinfunction "PB13_2") (pintype "passive"))
    )
    (net (code "28") (name "/B14") (class "Default")
      (node (ref "P1") (pin "3") (pinfunction "3_3") (pintype "passive"))
      (node (ref "P12") (pin "5") (pinfunction "5_5") (pintype "passive"))
      (node (ref "U1") (pin "3") (pinfunction "PB14_3") (pintype "passive"))
    )
    (net (code "29") (name "/B15") (class "Default")
      (node (ref "P1") (pin "4") (pinfunction "4_4") (pintype "passive"))
      (node (ref "P12") (pin "6") (pinfunction "6_6") (pintype "passive"))
      (node (ref "U1") (pin "4") (pinfunction "PB15_4") (pintype "passive"))
    )
    (net (code "30") (name "/OSC32_IN") (class "Default")
      (node (ref "P2") (pin "18") (pinfunction "18_18") (pintype "passive"))
      (node (ref "U1") (pin "23") (pinfunction "PC14_23") (pintype "passive"))
    )
    (net (code "31") (name "/OSC32_OUT") (class "Default")
      (node (ref "P2") (pin "17") (pinfunction "17_17") (pintype "passive"))
      (node (ref "U1") (pin "24") (pinfunction "PC15_24") (pintype "passive"))
    )
    (net (code "32") (name "/TAMPER-RTC") (class "Default")
      (node (ref "P2") (pin "19") (pinfunction "19_19") (pintype "passive"))
      (node (ref "U1") (pin "22") (pinfunction "PC13_22") (pintype "passive"))
    )
    (net (code "33") (name "GND") (class "Default")
      (node (ref "C1") (pin "2") (pinfunction "2_2") (pintype "passive"))
      (node (ref "C10") (pin "2") (pinfunction "2_2") (pintype "passive"))
      (node (ref "C11") (pin "2") (pinfunction "2_2") (pintype "passive"))
      (node (ref "C12") (pin "2") (pinfunction "2_2") (pintype "passive"))
      (node (ref "C13") (pin "1") (pinfunction "1_1") (pintype "passive"))
      (node (ref "C14") (pin "2") (pinfunction "2_2") (pintype "passive"))
      (node (ref "C15") (pin "1") (pinfunction "1_1") (pintype "passive"))
      (node (ref "C16") (pin "1") (pinfunction "1_1") (pintype "passive"))
      (node (ref "C17") (pin "1") (pinfunction "1_1") (pintype "passive"))
      (node (ref "C18") (pin "1") (pinfunction "1_1") (pintype "passive"))
      (node (ref "C19") (pin "1") (pinfunction "1_1") (pintype "passive"))
      (node (ref "C2") (pin "1") (pinfunction "1_1") (pintype "passive"))
      (node (ref "C20") (pin "1") (pinfunction "1_1") (pintype "passive"))
      (node (ref "C21") (pin "1") (pinfunction "1_1") (pintype "passive"))
      (node (ref "C22") (pin "1") (pinfunction "1_1") (pintype "passive"))
      (node (ref "C23") (pin "1") (pinfunction "1_1") (pintype "passive"))
      (node (ref "C24") (pin "2") (pinfunction "2_2") (pintype "passive"))
      (node (ref "C25") (pin "2") (pinfunction "2_2") (pintype "passive"))
      (node (ref "C26") (pin "1") (pinfunction "1_1") (pintype "passive"))
      (node (ref "C27") (pin "1") (pinfunction "1_1") (pintype "passive"))
      (node (ref "C28") (pin "1") (pinfunction "1_1") (pintype "passive"))
      (node (ref "C29") (pin "1") (pinfunction "1_1") (pintype "passive"))
      (node (ref "C3") (pin "1") (pinfunction "1_1") (pintype "passive"))
      (node (ref "C5") (pin "2") (pinfunction "2_2") (pintype "passive"))
      (node (ref "C6") (pin "2") (pinfunction "2_2") (pintype "passive"))
      (node (ref "C7") (pin "2") (pinfunction "2_2") (pintype "passive"))
      (node (ref "C8") (pin "2") (pinfunction "2_2") (pintype "passive"))
      (node (ref "C9") (pin "2") (pinfunction "2_2") (pintype "passive"))
      (node (ref "DC1") (pin "2") (pinfunction "2_2") (pintype "passive"))
      (node (ref "DC1") (pin "3") (pinfunction "3_3") (pintype "passive"))
      (node (ref "LED1") (pin "2") (pinfunction "-_2") (pintype "passive"))
      (node (ref "LED2") (pin "2") (pinfunction "-_2") (pintype "passive"))
      (node (ref "LED3") (pin "2") (pinfunction "-_2") (pintype "passive"))
      (node (ref "LED4") (pin "2") (pinfunction "-_2") (pintype "passive"))
      (node (ref "LED5") (pin "2") (pinfunction "-_2") (pintype "passive"))
      (node (ref "M1") (pin "1") (pinfunction "1_1") (pintype "passive"))
      (node (ref "M2") (pin "1") (pinfunction "1_1") (pintype "passive"))
      (node (ref "M3") (pin "1") (pinfunction "1_1") (pintype "passive"))
      (node (ref "M4") (pin "1") (pinfunction "1_1") (pintype "passive"))
      (node (ref "M5") (pin "1") (pinfunction "1_1") (pintype "passive"))
      (node (ref "M6") (pin "1") (pinfunction "1_1") (pintype "passive"))
      (node (ref "M7") (pin "1") (pinfunction "1_1") (pintype "passive"))
      (node (ref "M8") (pin "1") (pinfunction "1_1") (pintype "passive"))
      (node (ref "P1") (pin "19") (pinfunction "19_19") (pintype "passive"))
      (node (ref "P10") (pin "2") (pinfunction "2_2") (pintype "passive"))
      (node (ref "P11") (pin "1") (pinfunction "1_1") (pintype "passive"))
      (node (ref "P12") (pin "1") (pinfunction "1_1") (pintype "passive"))
      (node (ref "P13") (pin "3") (pinfunction "3_3") (pintype "passive"))
      (node (ref "P14") (pin "3") (pinfunction "3_3") (pintype "passive"))
      (node (ref "P15") (pin "3") (pinfunction "3_3") (pintype "passive"))
      (node (ref "P16") (pin "3") (pinfunction "3_3") (pintype "passive"))
      (node (ref "P17") (pin "3") (pinfunction "3_3") (pintype "passive"))
      (node (ref "P18") (pin "3") (pinfunction "3_3") (pintype "passive"))
      (node (ref "P19") (pin "3") (pinfunction "3_3") (pintype "passive"))
      (node (ref "P2") (pin "1") (pinfunction "1_1") (pintype "passive"))
      (node (ref "P2") (pin "2") (pinfunction "2_2") (pintype "passive"))
      (node (ref "P3") (pin "1") (pinfunction "1_1") (pintype "passive"))
      (node (ref "P4") (pin "1") (pinfunction "1_1") (pintype "passive"))
      (node (ref "P4") (pin "2") (pinfunction "2_2") (pintype "passive"))
      (node (ref "P4") (pin "3") (pinfunction "3_3") (pintype "passive"))
      (node (ref "P8") (pin "2") (pinfunction "2_2") (pintype "passive"))
      (node (ref "P9") (pin "2") (pinfunction "2_2") (pintype "passive"))
      (node (ref "Q2") (pin "1") (pinfunction "S_1") (pintype "passive"))
      (node (ref "Q2") (pin "2") (pinfunction "S_2") (pintype "passive"))
      (node (ref "Q2") (pin "3") (pinfunction "S_3") (pintype "passive"))
      (node (ref "R1") (pin "2") (pinfunction "2_2") (pintype "passive"))
      (node (ref "R10") (pin "2") (pinfunction "2_2") (pintype "passive"))
      (node (ref "R2") (pin "2") (pinfunction "2_2") (pintype "passive"))
      (node (ref "SW1") (pin "1") (pinfunction "1_1") (pintype "passive"))
      (node (ref "SW2") (pin "1") (pinfunction "1_1") (pintype "passive"))
      (node (ref "SW3") (pin "1") (pinfunction "1_1") (pintype "passive"))
      (node (ref "SW4") (pin "1") (pinfunction "1_1") (pintype "passive"))
      (node (ref "U1") (pin "19") (pinfunction "GND_19") (pintype "passive"))
      (node (ref "U1") (pin "39") (pinfunction "GND_39") (pintype "passive"))
      (node (ref "U1") (pin "40") (pinfunction "GND_40") (pintype "passive"))
      (node (ref "U2") (pin "6") (pinfunction "GND_6") (pintype "passive"))
      (node (ref "U3") (pin "7") (pinfunction "GND_7") (pintype "passive"))
      (node (ref "U3") (pin "8") (pinfunction "GND_8") (pintype "passive"))
      (node (ref "U4") (pin "2") (pinfunction "GND_2") (pintype "passive"))
      (node (ref "U5") (pin "2") (pinfunction "GND_2") (pintype "passive"))
    )
    (net (code "34") (name "Net-(L2-Pad1)") (class "Default")
      (node (ref "L2") (pin "1") (pinfunction "1_1") (pintype "passive"))
      (node (ref "U3") (pin "5") (pinfunction "SW_5") (pintype "passive"))
      (node (ref "U3") (pin "6") (pinfunction "SW_6") (pintype "passive"))
    )
    (net (code "35") (name "Net-(LED1-+)") (class "Default")
      (node (ref "LED1") (pin "1") (pinfunction "+_1") (pintype "passive"))
      (node (ref "R6") (pin "1") (pinfunction "1_1") (pintype "passive"))
    )
    (net (code "36") (name "Net-(LED2-+)") (class "Default")
      (node (ref "LED2") (pin "1") (pinfunction "+_1") (pintype "passive"))
      (node (ref "R11") (pin "1") (pinfunction "1_1") (pintype "passive"))
    )
    (net (code "37") (name "Net-(LED3-+)") (class "Default")
      (node (ref "LED3") (pin "1") (pinfunction "+_1") (pintype "passive"))
      (node (ref "R12") (pin "1") (pinfunction "1_1") (pintype "passive"))
    )
    (net (code "38") (name "Net-(LED4-+)") (class "Default")
      (node (ref "LED4") (pin "1") (pinfunction "+_1") (pintype "passive"))
      (node (ref "R13") (pin "1") (pinfunction "1_1") (pintype "passive"))
    )
    (net (code "39") (name "Net-(LED5-+)") (class "Default")
      (node (ref "LED5") (pin "1") (pinfunction "+_1") (pintype "passive"))
      (node (ref "R14") (pin "1") (pinfunction "1_1") (pintype "passive"))
    )
    (net (code "40") (name "Net-(P13-Pad1)") (class "Default")
      (node (ref "P13") (pin "1") (pinfunction "1_1") (pintype "passive"))
      (node (ref "R15") (pin "2") (pinfunction "2_2") (pintype "passive"))
    )
    (net (code "41") (name "Net-(P14-Pad1)") (class "Default")
      (node (ref "P14") (pin "1") (pinfunction "1_1") (pintype "passive"))
      (node (ref "R16") (pin "2") (pinfunction "2_2") (pintype "passive"))
    )
    (net (code "42") (name "Net-(P15-Pad1)") (class "Default")
      (node (ref "P15") (pin "1") (pinfunction "1_1") (pintype "passive"))
      (node (ref "R17") (pin "2") (pinfunction "2_2") (pintype "passive"))
    )
    (net (code "43") (name "Net-(P16-Pad1)") (class "Default")
      (node (ref "P16") (pin "1") (pinfunction "1_1") (pintype "passive"))
      (node (ref "R18") (pin "2") (pinfunction "2_2") (pintype "passive"))
    )
    (net (code "44") (name "Net-(P17-Pad1)") (class "Default")
      (node (ref "P17") (pin "1") (pinfunction "1_1") (pintype "passive"))
      (node (ref "R19") (pin "2") (pinfunction "2_2") (pintype "passive"))
    )
    (net (code "45") (name "Net-(P18-Pad1)") (class "Default")
      (node (ref "P18") (pin "1") (pinfunction "1_1") (pintype "passive"))
      (node (ref "R20") (pin "2") (pinfunction "2_2") (pintype "passive"))
    )
    (net (code "46") (name "Net-(P19-Pad1)") (class "Default")
      (node (ref "P19") (pin "1") (pinfunction "1_1") (pintype "passive"))
      (node (ref "R21") (pin "2") (pinfunction "2_2") (pintype "passive"))
    )
    (net (code "47") (name "Net-(Q1-G)") (class "Default")
      (node (ref "Q1") (pin "4") (pinfunction "G_4") (pintype "passive"))
      (node (ref "U2") (pin "2") (pinfunction "HG_2") (pintype "passive"))
    )
    (net (code "48") (name "Net-(Q2-G)") (class "Default")
      (node (ref "Q2") (pin "4") (pinfunction "G_4") (pintype "passive"))
      (node (ref "U2") (pin "5") (pinfunction "LG_5") (pintype "passive"))
    )
    (net (code "49") (name "Net-(R3-BOT)") (class "Default")
      (node (ref "R3") (pin "2") (pinfunction "BOT_2") (pintype "passive"))
      (node (ref "R3") (pin "ADJ") (pinfunction "ADJ_ADJ") (pintype "passive"))
      (node (ref "R4") (pin "2") (pinfunction "2_2") (pintype "passive"))
    )
    (net (code "50") (name "Net-(R3-TOP)") (class "Default")
      (node (ref "R2") (pin "1") (pinfunction "1_1") (pintype "passive"))
      (node (ref "R3") (pin "1") (pinfunction "TOP_1") (pintype "passive"))
      (node (ref "U2") (pin "7") (pinfunction "FB_7") (pintype "passive"))
    )
    (net (code "51") (name "Net-(U1-+5V)") (class "Default")
      (node (ref "P1") (pin "18") (pinfunction "18_18") (pintype "passive"))
      (node (ref "U1") (pin "18") (pinfunction "+5V_18") (pintype "passive"))
    )
    (net (code "52") (name "Net-(U1-RESET)") (class "Default")
      (node (ref "P2") (pin "4") (pinfunction "4_4") (pintype "passive"))
      (node (ref "U1") (pin "37") (pinfunction "RESET_37") (pintype "passive"))
    )
    (net (code "53") (name "Net-(U1-VBAT)") (class "Default")
      (node (ref "P2") (pin "20") (pinfunction "20_20") (pintype "passive"))
      (node (ref "U1") (pin "21") (pinfunction "VBAT_21") (pintype "passive"))
    )
    (net (code "54") (name "Net-(U2-BST)") (class "Default")
      (node (ref "C4") (pin "2") (pinfunction "2_2") (pintype "passive"))
      (node (ref "U2") (pin "4") (pinfunction "BST_4") (pintype "passive"))
    )
    (net (code "55") (name "Net-(U2-CSP)") (class "Default")
      (node (ref "C5") (pin "1") (pinfunction "1_1") (pintype "passive"))
      (node (ref "C6") (pin "1") (pinfunction "1_1") (pintype "passive"))
      (node (ref "C7") (pin "1") (pinfunction "1_1") (pintype "passive"))
      (node (ref "L1") (pin "2") (pinfunction "2_2") (pintype "passive"))
      (node (ref "R5") (pin "1") (pinfunction "1_1") (pintype "passive"))
      (node (ref "U2") (pin "8") (pinfunction "CSP_8") (pintype "passive"))
    )
    (net (code "56") (name "Net-(U2-FS)") (class "Default")
      (node (ref "R1") (pin "1") (pinfunction "1_1") (pintype "passive"))
      (node (ref "U2") (pin "10") (pinfunction "FS_10") (pintype "passive"))
    )
    (net (code "57") (name "Net-(U2-SW)") (class "Default")
      (node (ref "C4") (pin "1") (pinfunction "1_1") (pintype "passive"))
      (node (ref "L1") (pin "1") (pinfunction "1_1") (pintype "passive"))
      (node (ref "Q1") (pin "1") (pinfunction "S_1") (pintype "passive"))
      (node (ref "Q1") (pin "2") (pinfunction "S_2") (pintype "passive"))
      (node (ref "Q1") (pin "3") (pinfunction "S_3") (pintype "passive"))
      (node (ref "Q2") (pin "5") (pinfunction "D_5") (pintype "passive"))
      (node (ref "Q2") (pin "6") (pinfunction "D_6") (pintype "passive"))
      (node (ref "Q2") (pin "7") (pinfunction "D_7") (pintype "passive"))
      (node (ref "Q2") (pin "8") (pinfunction "D_8") (pintype "passive"))
      (node (ref "Q2") (pin "9") (pinfunction "D_9") (pintype "passive"))
      (node (ref "U2") (pin "3") (pinfunction "SW_3") (pintype "passive"))
    )
    (net (code "58") (name "Net-(U2-VIN)") (class "Default")
      (node (ref "C1") (pin "1") (pinfunction "1_1") (pintype "passive"))
      (node (ref "C2") (pin "2") (pinfunction "2_2") (pintype "passive"))
      (node (ref "C3") (pin "2") (pinfunction "2_2") (pintype "passive"))
      (node (ref "Q1") (pin "5") (pinfunction "D_5") (pintype "passive"))
      (node (ref "Q1") (pin "6") (pinfunction "D_6") (pintype "passive"))
      (node (ref "Q1") (pin "7") (pinfunction "D_7") (pintype "passive"))
      (node (ref "Q1") (pin "8") (pinfunction "D_8") (pintype "passive"))
      (node (ref "Q1") (pin "9") (pinfunction "D_9") (pintype "passive"))
      (node (ref "S2") (pin "3") (pintype "passive"))
      (node (ref "U2") (pin "1") (pinfunction "VIN_1") (pintype "passive"))
    )
    (net (code "59") (name "Net-(U3-EN)") (class "Default")
      (node (ref "R7") (pin "1") (pinfunction "1_1") (pintype "passive"))
      (node (ref "U3") (pin "3") (pinfunction "EN_3") (pintype "passive"))
    )
    (net (code "60") (name "Net-(U3-NC)") (class "Default")
      (node (ref "R8") (pin "2") (pinfunction "2_2") (pintype "passive"))
      (node (ref "U3") (pin "2") (pinfunction "NC_2") (pintype "passive"))
    )
    (net (code "61") (name "Net-(U3-VFB)") (class "Default")
      (node (ref "R10") (pin "1") (pinfunction "1_1") (pintype "passive"))
      (node (ref "R9") (pin "2") (pinfunction "2_2") (pintype "passive"))
      (node (ref "U3") (pin "1") (pinfunction "VFB_1") (pintype "passive"))
    )
    (net (code "62") (name "VCC") (class "Default")
      (node (ref "DC1") (pin "1") (pinfunction "1_1") (pintype "passive"))
      (node (ref "P3") (pin "2") (pinfunction "2_2") (pintype "passive"))
      (node (ref "S1") (pin "2") (pintype "passive"))
    )
    (net (code "63") (name "VCCBAT") (class "Default")
      (node (ref "C11") (pin "1") (pinfunction "1_1") (pintype "passive"))
      (node (ref "C12") (pin "1") (pinfunction "1_1") (pintype "passive"))
      (node (ref "P5") (pin "1") (pinfunction "1_1") (pintype "passive"))
      (node (ref "P5") (pin "2") (pinfunction "2_2") (pintype "passive"))
      (node (ref "P5") (pin "3") (pinfunction "3_3") (pintype "passive"))
      (node (ref "R7") (pin "2") (pinfunction "2_2") (pintype "passive"))
      (node (ref "S1") (pin "3") (pintype "passive"))
      (node (ref "S2") (pin "2") (pintype "passive"))
      (node (ref "U3") (pin "4") (pinfunction "VIN_4") (pintype "passive"))
    )
    (net (code "64") (name "VCC_3.3V") (class "Default")
      (node (ref "C19") (pin "2") (pinfunction "2_2") (pintype "passive"))
      (node (ref "C20") (pin "2") (pinfunction "2_2") (pintype "passive"))
      (node (ref "C24") (pin "1") (pinfunction "1_1") (pintype "passive"))
      (node (ref "C25") (pin "1") (pinfunction "1_1") (pintype "passive"))
      (node (ref "P11") (pin "2") (pinfunction "2_2") (pintype "passive"))
      (node (ref "P12") (pin "2") (pinfunction "2_2") (pintype "passive"))
      (node (ref "P7") (pin "1") (pinfunction "1_1") (pintype "passive"))
      (node (ref "P7") (pin "2") (pinfunction "2_2") (pintype "passive"))
      (node (ref "P7") (pin "3") (pinfunction "3_3") (pintype "passive"))
      (node (ref "R13") (pin "2") (pinfunction "2_2") (pintype "passive"))
      (node (ref "R22") (pin "2") (pinfunction "2_2") (pintype "passive"))
      (node (ref "R23") (pin "2") (pinfunction "2_2") (pintype "passive"))
      (node (ref "R24") (pin "2") (pinfunction "2_2") (pintype "passive"))
      (node (ref "R25") (pin "2") (pinfunction "2_2") (pintype "passive"))
      (node (ref "T4") (pin "1") (pinfunction "T_1") (pintype "passive"))
      (node (ref "U5") (pin "5") (pinfunction "OUT_5") (pintype "passive"))
    )
    (net (code "65") (name "VCC_5V") (class "Default")
      (node (ref "C13") (pin "2") (pinfunction "2_2") (pintype "passive"))
      (node (ref "C14") (pin "1") (pinfunction "1_1") (pintype "passive"))
      (node (ref "C15") (pin "2") (pinfunction "2_2") (pintype "passive"))
      (node (ref "C18") (pin "2") (pinfunction "2_2") (pintype "passive"))
      (node (ref "C21") (pin "2") (pinfunction "2_2") (pintype "passive"))
      (node (ref "C22") (pin "2") (pinfunction "2_2") (pintype "passive"))
      (node (ref "C23") (pin "2") (pinfunction "2_2") (pintype "passive"))
      (node (ref "L2") (pin "2") (pinfunction "2_2") (pintype "passive"))
      (node (ref "P10") (pin "1") (pinfunction "1_1") (pintype "passive"))
      (node (ref "P6") (pin "1") (pinfunction "1_1") (pintype "passive"))
      (node (ref "P6") (pin "2") (pinfunction "2_2") (pintype "passive"))
      (node (ref "P6") (pin "3") (pinfunction "3_3") (pintype "passive"))
      (node (ref "P8") (pin "1") (pinfunction "1_1") (pintype "passive"))
      (node (ref "P9") (pin "1") (pinfunction "1_1") (pintype "passive"))
      (node (ref "R11") (pin "2") (pinfunction "2_2") (pintype "passive"))
      (node (ref "R8") (pin "1") (pinfunction "1_1") (pintype "passive"))
      (node (ref "R9") (pin "1") (pinfunction "1_1") (pintype "passive"))
      (node (ref "T2") (pin "1") (pinfunction "T_1") (pintype "passive"))
      (node (ref "U4") (pin "1") (pinfunction "IN_1") (pintype "passive"))
      (node (ref "U4") (pin "3") (pinfunction "EN_3") (pintype "passive"))
      (node (ref "U5") (pin "1") (pinfunction "IN_1") (pintype "passive"))
      (node (ref "U5") (pin "3") (pinfunction "EN_3") (pintype "passive"))
    )
    (net (code "66") (name "VCC_MCU_3.3V") (class "Default")
      (node (ref "C16") (pin "2") (pinfunction "2_2") (pintype "passive"))
      (node (ref "C17") (pin "2") (pinfunction "2_2") (pintype "passive"))
      (node (ref "P1") (pin "20") (pinfunction "20_20") (pintype "passive"))
      (node (ref "P2") (pin "3") (pinfunction "3_3") (pintype "passive"))
      (node (ref "R12") (pin "2") (pinfunction "2_2") (pintype "passive"))
      (node (ref "T3") (pin "1") (pinfunction "T_1") (pintype "passive"))
      (node (ref "U1") (pin "20") (pinfunction "+3.3V_20") (pintype "passive"))
      (node (ref "U1") (pin "38") (pinfunction "+3.3V_38") (pintype "passive"))
      (node (ref "U4") (pin "5") (pinfunction "OUT_5") (pintype "passive"))
    )
    (net (code "67") (name "VCC_Servo_5V") (class "Default")
      (node (ref "C10") (pin "1") (pinfunction "1_1") (pintype "passive"))
      (node (ref "C8") (pin "1") (pinfunction "1_1") (pintype "passive"))
      (node (ref "C9") (pin "1") (pinfunction "1_1") (pintype "passive"))
      (node (ref "P13") (pin "2") (pinfunction "2_2") (pintype "passive"))
      (node (ref "P14") (pin "2") (pinfunction "2_2") (pintype "passive"))
      (node (ref "P15") (pin "2") (pinfunction "2_2") (pintype "passive"))
      (node (ref "P16") (pin "2") (pinfunction "2_2") (pintype "passive"))
      (node (ref "P17") (pin "2") (pinfunction "2_2") (pintype "passive"))
      (node (ref "P18") (pin "2") (pinfunction "2_2") (pintype "passive"))
      (node (ref "P19") (pin "2") (pinfunction "2_2") (pintype "passive"))
      (node (ref "R4") (pin "1") (pinfunction "1_1") (pintype "passive"))
      (node (ref "R5") (pin "2") (pinfunction "2_2") (pintype "passive"))
      (node (ref "R6") (pin "2") (pinfunction "2_2") (pintype "passive"))
      (node (ref "T1") (pin "1") (pinfunction "T_1") (pintype "passive"))
      (node (ref "U2") (pin "9") (pinfunction "CSN_9") (pintype "passive"))
    )
    (net (code "68") (name "unconnected-(S1-Pad1)") (class "Default")
      (node (ref "S1") (pin "1") (pintype "passive+no_connect"))
    )
    (net (code "69") (name "unconnected-(S2-Pad1)") (class "Default")
      (node (ref "S2") (pin "1") (pintype "passive+no_connect"))
    )
    (net (code "70") (name "unconnected-(U4-NC-Pad4)") (class "Default")
      (node (ref "U4") (pin "4") (pinfunction "NC_4") (pintype "passive+no_connect"))
    )
    (net (code "71") (name "unconnected-(U5-NC-Pad4)") (class "Default")
      (node (ref "U5") (pin "4") (pinfunction "NC_4") (pintype "passive+no_connect"))
    )
  )
)
